# RS485.net
KiCad netlist of a schematic drawn in Altium Designer
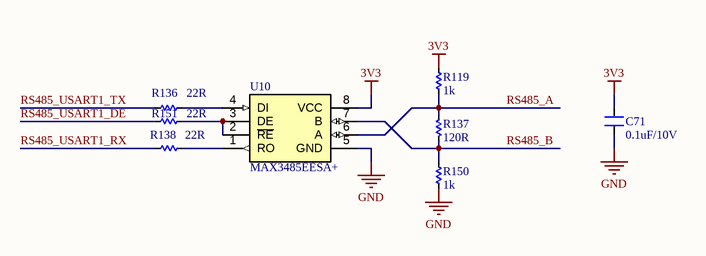
[diagram p0: RS485.SchDoc]

(export (version "E")
  (design (tool "Eeschema 10.0.6"))
  (components
    (comp (ref "C71")
      (value "0.1uF/10V")
      (footprint "CAP_C_1608X80")
      (libsource (lib "EXP_HW_V3") (part "Capacitors"))
    )
    (comp (ref "R119")
      (value "1k")
      (footprint "RES_C_1608X60")
      (description "SMD")
      (fields
        (field (name "MANUFACTURER") "Generic Components")
        (field (name "PUBLISHER") "Altium Hobart Technology Centre")
      )
      (libsource (lib "EXP_HW_V3") (part "Res SMD"))
    )
    (comp (ref "R136")
      (value "22R")
      (footprint "RES_C_1608X60")
      (description "SMD")
      (fields
        (field (name "MANUFACTURER") "Generic Components")
        (field (name "PUBLISHER") "Altium Hobart Technology Centre")
      )
      (libsource (lib "EXP_HW_V3") (part "Res SMD"))
    )
    (comp (ref "R137")
      (value "120R")
      (footprint "RES_C_1608X60")
      (description "SMD")
      (fields
        (field (name "MANUFACTURER") "Generic Components")
        (field (name "PUBLISHER") "Altium Hobart Technology Centre")
      )
      (libsource (lib "EXP_HW_V3") (part "Res SMD"))
    )
    (comp (ref "R138")
      (value "22R")
      (footprint "RES_C_1608X60")
      (description "SMD")
      (fields
        (field (name "MANUFACTURER") "Generic Components")
        (field (name "PUBLISHER") "Altium Hobart Technology Centre")
      )
      (libsource (lib "EXP_HW_V3") (part "Res SMD"))
    )
    (comp (ref "R150")
      (value "1k")
      (footprint "RES_C_1608X60")
      (description "SMD")
      (fields
        (field (name "MANUFACTURER") "Generic Components")
        (field (name "PUBLISHER") "Altium Hobart Technology Centre")
      )
      (libsource (lib "EXP_HW_V3") (part "Res SMD"))
    )
    (comp (ref "R151")
      (value "22R")
      (footprint "RES_C_1608X60")
      (description "SMD")
      (fields
        (field (name "MANUFACTURER") "Generic Components")
        (field (name "PUBLISHER") "Altium Hobart Technology Centre")
      )
      (libsource (lib "EXP_HW_V3") (part "Res SMD"))
    )
    (comp (ref "U10")
      (value "MAX3485EESA+")
      (footprint "SOIC8_3.9mm")
      (description "3.3V Powered, Â±15kV ESD-Protected, 12Mbps, Slew-Rate-Limited True RS-485/RS-422 Transceivers")
      (fields (field (name "MF") "Analog Devices"))
      (libsource (lib "EXP_HW_V3") (part "MAX3485EESA+"))
    )
  )
  (nets
    (net (code "1") (name "/RS485_A") (class "Default")
      (node (ref "R119") (pin "1") (pinfunction "1_1") (pintype "passive"))
      (node (ref "R137") (pin "1") (pinfunction "1_1") (pintype "passive"))
      (node (ref "U10") (pin "6") (pinfunction "A_6") (pintype "bidirectional"))
    )
    (net (code "2") (name "/RS485_B") (class "Default")
      (node (ref "R137") (pin "2") (pinfunction "2_2") (pintype "passive"))
      (node (ref "R150") (pin "2") (pinfunction "2_2") (pintype "passive"))
      (node (ref "U10") (pin "7") (pinfunction "B_7") (pintype "bidirectional"))
    )
    (net (code "3") (name "/RS485_USART1_DE") (class "Default")
      (node (ref "R151") (pin "1") (pinfunction "1_1") (pintype "passive"))
    )
    (net (code "4") (name "/RS485_USART1_RX") (class "Default")
      (node (ref "R138") (pin "1") (pinfunction "1_1") (pintype "passive"))
    )
    (net (code "5") (name "/RS485_USART1_TX") (class "Default")
      (node (ref "R136") (pin "1") (pinfunction "1_1") (pintype "passive"))
    )
    (net (code "6") (name "3V3") (class "Default")
      (node (ref "C71") (pin "2") (pinfunction "2_2") (pintype "passive"))
      (node (ref "R119") (pin "2") (pinfunction "2_2") (pintype "passive"))
      (node (ref "U10") (pin "8") (pinfunction "VCC_8") (pintype "power_in"))
    )
    (net (code "7") (name "GND") (class "Default")
      (node (ref "C71") (pin "1") (pinfunction "1_1") (pintype "passive"))
      (node (ref "R150") (pin "1") (pinfunction "1_1") (pintype "passive"))
      (node (ref "U10") (pin "5") (pinfunction "GND_5") (pintype "power_in"))
    )
    (net (code "8") (name "Net-(U10-DE)") (class "Default")
      (node (ref "R151") (pin "2") (pinfunction "2_2") (pintype "passive"))
      (node (ref "U10") (pin "2") (pinfunction "~{RE}_2") (pintype "passive"))
      (node (ref "U10") (pin "3") (pinfunction "DE_3") (pintype "passive"))
    )
    (net (code "9") (name "Net-(U10-DI)") (class "Default")
      (node (ref "R136") (pin "2") (pinfunction "2_2") (pintype "passive"))
      (node (ref "U10") (pin "4") (pinfunction "DI_4") (pintype "input"))
    )
    (net (code "10") (name "Net-(U10-RO)") (class "Default")
      (node (ref "R138") (pin "2") (pinfunction "2_2") (pintype "passive"))
      (node (ref "U10") (pin "1") (pinfunction "RO_1") (pintype "output"))
    )
  )
)
